# STM32.net
KiCad netlist of a schematic drawn in Altium Designer
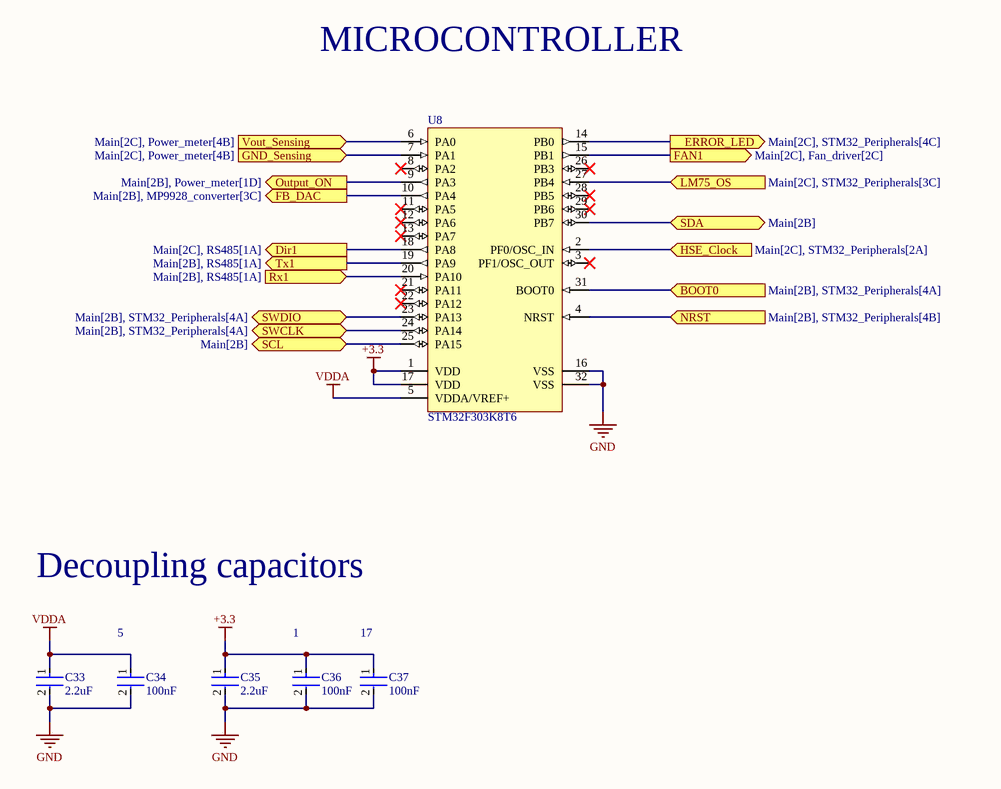
[diagram p0: STM32.SchDoc]

(export (version "E")
  (design (tool "Eeschema 10.0.6"))
  (components
    (comp (ref "C33")
      (value "2.2uF")
      (footprint "FP-0805-L_2_01_0_2-W_1_25-IPC_B")
      (description "General Purpose Ceramic Capacitor, 0805, 10nF, 10%, X7R, 15%, 100V")
      (fields (field (name "VOLTAGE") "100V") (field (name "TOLERANCE") "10%"))
      (libsource (lib "Altium Content Vault") (part "b4654b650e69147ec39a6b967a45e02"))
    )
    (comp (ref "C34")
      (value "100nF")
      (footprint "FP-CGA3E-0_3-0_1-IPC_A")
      (description "Cap Ceramic 100nF 50V X7R 10% Pad SMD 0603 +125°C Automotive T/R")
      (fields (field (name "TOLERANCE") "10%") (field (name "VOLTAGE") "50V"))
      (libsource (lib "Altium Content Vault") (part "b4654b650e69147ec39a6b967a45e02"))
    )
    (comp (ref "C35")
      (value "2.2uF")
      (footprint "FP-0805-L_2_01_0_2-W_1_25-IPC_B")
      (description "General Purpose Ceramic Capacitor, 0805, 10nF, 10%, X7R, 15%, 100V")
      (fields (field (name "VOLTAGE") "100V") (field (name "TOLERANCE") "10%"))
      (libsource (lib "Altium Content Vault") (part "b4654b650e69147ec39a6b967a45e02"))
    )
    (comp (ref "C36")
      (value "100nF")
      (footprint "FP-CGA3E-0_3-0_1-IPC_A")
      (description "Cap Ceramic 100nF 50V X7R 10% Pad SMD 0603 +125°C Automotive T/R")
      (fields (field (name "TOLERANCE") "10%") (field (name "VOLTAGE") "50V"))
      (libsource (lib "Altium Content Vault") (part "b4654b650e69147ec39a6b967a45e02"))
    )
    (comp (ref "C37")
      (value "100nF")
      (footprint "FP-CGA3E-0_3-0_1-IPC_A")
      (description "Cap Ceramic 100nF 50V X7R 10% Pad SMD 0603 +125°C Automotive T/R")
      (fields (field (name "TOLERANCE") "10%") (field (name "VOLTAGE") "50V"))
      (libsource (lib "Altium Content Vault") (part "b4654b650e69147ec39a6b967a45e02"))
    )
    (comp (ref "U8")
      (value "STM32F303K8T6")
      (footprint "STM-LQFP32_M")
      (libsource (lib "Altium Content Vault") (part "MC-ARM-STM32F303-LQFP32"))
    )
  )
  (nets
    (net (code "1") (name "+3.3") (class "Default")
      (node (ref "C35") (pin "1") (pinfunction "1_1") (pintype "passive"))
      (node (ref "C36") (pin "1") (pinfunction "1_1") (pintype "passive"))
      (node (ref "C37") (pin "1") (pinfunction "1_1") (pintype "passive"))
      (node (ref "U8") (pin "1") (pinfunction "VDD_1") (pintype "power_in"))
      (node (ref "U8") (pin "17") (pinfunction "VDD_17") (pintype "power_in"))
    )
    (net (code "3") (name "/BOOT0") (class "Default")
      (node (ref "U8") (pin "31") (pinfunction "BOOT0_31") (pintype "input"))
    )
    (net (code "4") (name "/Dir1") (class "Default")
      (node (ref "U8") (pin "18") (pinfunction "PA8_18") (pintype "output"))
    )
    (net (code "5") (name "/ERROR_LED") (class "Default")
      (node (ref "U8") (pin "14") (pinfunction "PB0_14") (pintype "output"))
    )
    (net (code "6") (name "/FAN1") (class "Default")
      (node (ref "U8") (pin "15") (pinfunction "PB1_15") (pintype "output"))
    )
    (net (code "7") (name "/FB_DAC") (class "Default")
      (node (ref "U8") (pin "10") (pinfunction "PA4_10") (pintype "output"))
    )
    (net (code "8") (name "/GND_Sensing") (class "Default")
      (node (ref "U8") (pin "7") (pinfunction "PA1_7") (pintype "input"))
    )
    (net (code "9") (name "/HSE_Clock") (class "Default")
      (node (ref "U8") (pin "2") (pinfunction "PF0/OSC_IN_2") (pintype "input"))
    )
    (net (code "10") (name "/LM75_OS") (class "Default")
      (node (ref "U8") (pin "27") (pinfunction "PB4_27") (pintype "input"))
    )
    (net (code "11") (name "/NRST") (class "Default")
      (node (ref "U8") (pin "4") (pinfunction "NRST_4") (pintype "input"))
    )
    (net (code "12") (name "/Output_ON") (class "Default")
      (node (ref "U8") (pin "9") (pinfunction "PA3_9") (pintype "output"))
    )
    (net (code "13") (name "/Rx1") (class "Default")
      (node (ref "U8") (pin "20") (pinfunction "PA10_20") (pintype "input"))
    )
    (net (code "14") (name "/SCL") (class "Default")
      (node (ref "U8") (pin "25") (pinfunction "PA15_25") (pintype "bidirectional"))
    )
    (net (code "15") (name "/SDA") (class "Default")
      (node (ref "U8") (pin "30") (pinfunction "PB7_30") (pintype "bidirectional"))
    )
    (net (code "16") (name "/SWCLK") (class "Default")
      (node (ref "U8") (pin "24") (pinfunction "PA14_24") (pintype "bidirectional"))
    )
    (net (code "17") (name "/SWDIO") (class "Default")
      (node (ref "U8") (pin "23") (pinfunction "PA13_23") (pintype "bidirectional"))
    )
    (net (code "18") (name "/Tx1") (class "Default")
      (node (ref "U8") (pin "19") (pinfunction "PA9_19") (pintype "output"))
    )
    (net (code "19") (name "/Vout_Sensing") (class "Default")
      (node (ref "U8") (pin "6") (pinfunction "PA0_6") (pintype "input"))
    )
    (net (code "20") (name "GND") (class "Default")
      (node (ref "C33") (pin "2") (pinfunction "2_2") (pintype "passive"))
      (node (ref "C34") (pin "2") (pinfunction "2_2") (pintype "passive"))
      (node (ref "C35") (pin "2") (pinfunction "2_2") (pintype "passive"))
      (node (ref "C36") (pin "2") (pinfunction "2_2") (pintype "passive"))
      (node (ref "C37") (pin "2") (pinfunction "2_2") (pintype "passive"))
      (node (ref "U8") (pin "16") (pinfunction "VSS_16") (pintype "power_in"))
      (node (ref "U8") (pin "32") (pinfunction "VSS_32") (pintype "power_in"))
    )
    (net (code "21") (name "VDDA") (class "Default")
      (node (ref "C33") (pin "1") (pinfunction "1_1") (pintype "passive"))
      (node (ref "C34") (pin "1") (pinfunction "1_1") (pintype "passive"))
      (node (ref "U8") (pin "5") (pinfunction "VDDA/VREF+_5") (pintype "power_in"))
    )
    (net (code "22") (name "unconnected-(U8-PA2-Pad8)") (class "Default")
      (node (ref "U8") (pin "8") (pinfunction "PA2_8") (pintype "bidirectional+no_connect"))
    )
    (net (code "23") (name "unconnected-(U8-PA5-Pad11)") (class "Default")
      (node (ref "U8") (pin "11") (pinfunction "PA5_11") (pintype "bidirectional+no_connect"))
    )
    (net (code "24") (name "unconnected-(U8-PA6-Pad12)") (class "Default")
      (node (ref "U8") (pin "12") (pinfunction "PA6_12") (pintype "bidirectional+no_connect"))
    )
    (net (code "25") (name "unconnected-(U8-PA7-Pad13)") (class "Default")
      (node (ref "U8") (pin "13") (pinfunction "PA7_13") (pintype "bidirectional+no_connect"))
    )
    (net (code "26") (name "unconnected-(U8-PA11-Pad21)") (class "Default")
      (node (ref "U8") (pin "21") (pinfunction "PA11_21") (pintype "bidirectional+no_connect"))
    )
    (net (code "27") (name "unconnected-(U8-PA12-Pad22)") (class "Default")
      (node (ref "U8") (pin "22") (pinfunction "PA12_22") (pintype "bidirectional+no_connect"))
    )
    (net (code "28") (name "unconnected-(U8-PB3-Pad26)") (class "Default")
      (node (ref "U8") (pin "26") (pinfunction "PB3_26") (pintype "bidirectional+no_connect"))
    )
    (net (code "29") (name "unconnected-(U8-PB5-Pad28)") (class "Default")
      (node (ref "U8") (pin "28") (pinfunction "PB5_28") (pintype "bidirectional+no_connect"))
    )
    (net (code "30") (name "unconnected-(U8-PB6-Pad29)") (class "Default")
      (node (ref "U8") (pin "29") (pinfunction "PB6_29") (pintype "bidirectional+no_connect"))
    )
    (net (code "31") (name "unconnected-(U8-PF1{slash}OSC_OUT-Pad3)") (class "Default")
      (node (ref "U8") (pin "3") (pinfunction "PF1/OSC_OUT_3") (pintype "bidirectional+no_connect"))
    )
  )
)
